# NETWORK_RS485.net
KiCad netlist of a schematic drawn in Altium Designer
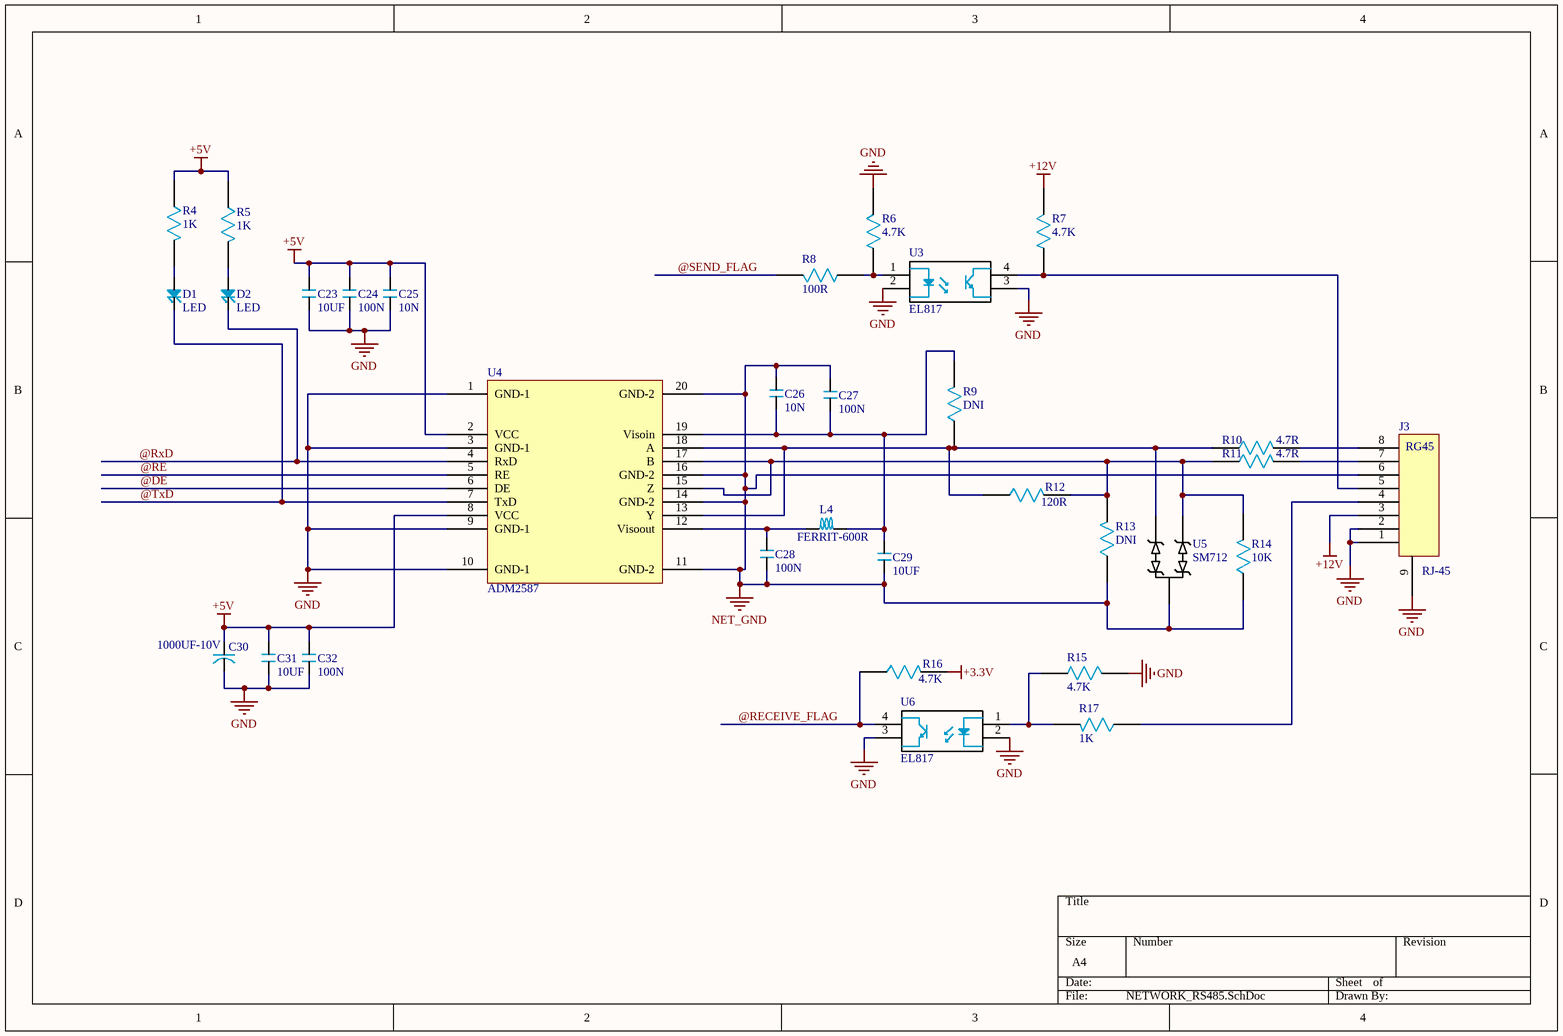
[diagram p0: NETWORK_RS485.SchDoc]

(export (version "E")
  (design (tool "Eeschema 10.0.6"))
  (components
    (comp (ref "C23") (value "10UF") (footprint "0603") (libsource (lib "R_L_C_V") (part "CAP")))
    (comp (ref "C24") (value "100N") (footprint "0603") (libsource (lib "R_L_C_V") (part "CAP")))
    (comp (ref "C25") (value "10N") (footprint "0603") (libsource (lib "R_L_C_V") (part "CAP")))
    (comp (ref "C26") (value "10N") (footprint "1206") (libsource (lib "R_L_C_V") (part "CAP")))
    (comp (ref "C27") (value "100N") (footprint "1206") (libsource (lib "R_L_C_V") (part "CAP")))
    (comp (ref "C28") (value "100N") (footprint "1206") (libsource (lib "R_L_C_V") (part "CAP")))
    (comp (ref "C29") (value "10UF") (footprint "1206") (libsource (lib "R_L_C_V") (part "CAP")))
    (comp (ref "C30") (value "1000UF-10V") (footprint "RB.2/.4") (libsource (lib "My_lib") (part "CAP_POL")))
    (comp (ref "C31") (value "10UF") (footprint "0603") (libsource (lib "R_L_C_V") (part "CAP")))
    (comp (ref "C32") (value "100N") (footprint "0603") (libsource (lib "R_L_C_V") (part "CAP")))
    (comp (ref "D1") (value "LED") (footprint "0603") (libsource (lib "My_lib") (part "LED")))
    (comp (ref "D2") (value "LED") (footprint "0603") (libsource (lib "My_lib") (part "LED")))
    (comp (ref "J3") (value "RJ-45") (footprint "RJ-45") (libsource (lib "CONNECTOR") (part "RJ-45")))
    (comp (ref "L4") (value "FERRIT-600R") (footprint "1206") (libsource (lib "R_L_C_V") (part "SELF")))
    (comp (ref "R4") (value "1K") (footprint "0603") (libsource (lib "My_lib") (part "RES")))
    (comp (ref "R5") (value "1K") (footprint "0603") (libsource (lib "My_lib") (part "RES")))
    (comp (ref "R6") (value "4.7K") (footprint "1206") (libsource (lib "My_lib") (part "RES")))
    (comp (ref "R7") (value "4.7K") (footprint "1206") (libsource (lib "My_lib") (part "RES")))
    (comp (ref "R8") (value "100R") (footprint "1206") (libsource (lib "My_lib") (part "RES")))
    (comp (ref "R9") (value "DNI") (footprint "1206") (libsource (lib "My_lib") (part "RES")))
    (comp (ref "R10") (value "4.7R") (footprint "1206") (libsource (lib "My_lib") (part "RES")))
    (comp (ref "R11") (value "4.7R") (footprint "1206") (libsource (lib "My_lib") (part "RES")))
    (comp (ref "R12") (value "120R") (footprint "1206") (libsource (lib "My_lib") (part "RES")))
    (comp (ref "R13") (value "DNI") (footprint "1206") (libsource (lib "My_lib") (part "RES")))
    (comp (ref "R14") (value "10K") (footprint "1206") (libsource (lib "My_lib") (part "RES")))
    (comp (ref "R15") (value "4.7K") (footprint "1206") (libsource (lib "My_lib") (part "RES")))
    (comp (ref "R16") (value "4.7K") (footprint "1206") (libsource (lib "My_lib") (part "RES")))
    (comp (ref "R17") (value "1K") (footprint "1206") (libsource (lib "My_lib") (part "RES")))
    (comp (ref "U3") (value "EL817") (footprint "DIP4") (libsource (lib "My_lib") (part "TLP521")))
    (comp (ref "U4") (value "ADM2587") (footprint "SOIC20_W") (libsource (lib "MY_IC") (part "AMD2582")))
    (comp (ref "U5") (value "SM712") (footprint "SOT-23") (libsource (lib "MY_IC") (part "SM712")))
    (comp (ref "U6") (value "EL817") (footprint "DIP4") (libsource (lib "My_lib") (part "TLP521")))
  )
  (nets
    (net (code "1") (name "+3.3V") (class "Default") (node (ref "R16") (pin "2") (pintype "passive")))
    (net (code "2") (name "+5V") (class "Default")
      (node (ref "C23") (pin "2") (pintype "passive"))
      (node (ref "C24") (pin "2") (pintype "passive"))
      (node (ref "C25") (pin "1") (pintype "passive"))
      (node (ref "C30") (pin "1") (pintype "passive"))
      (node (ref "C31") (pin "2") (pintype "passive"))
      (node (ref "C32") (pin "2") (pintype "passive"))
      (node (ref "R4") (pin "1") (pintype "passive"))
      (node (ref "R5") (pin "1") (pintype "passive"))
      (node (ref "U4") (pin "2") (pinfunction "VCC_2") (pintype "passive"))
      (node (ref "U4") (pin "8") (pinfunction "VCC_8") (pintype "passive"))
    )
    (net (code "3") (name "+12V") (class "Default")
      (node (ref "J3") (pin "3") (pinfunction "3_3") (pintype "passive"))
      (node (ref "R7") (pin "1") (pintype "passive"))
    )
    (net (code "4") (name "/@DE") (class "Default")
      (node (ref "U4") (pin "6") (pinfunction "DE_6") (pintype "passive"))
    )
    (net (code "5") (name "/@RE") (class "Default")
      (node (ref "U4") (pin "5") (pinfunction "RE_5") (pintype "passive"))
    )
    (net (code "6") (name "/@RECEIVE_FLAG") (class "Default")
      (node (ref "R16") (pin "1") (pintype "passive"))
      (node (ref "U6") (pin "4") (pintype "passive"))
    )
    (net (code "7") (name "/@RxD") (class "Default")
      (node (ref "D2") (pin "2") (pintype "passive"))
      (node (ref "U4") (pin "4") (pinfunction "RxD_4") (pintype "passive"))
    )
    (net (code "8") (name "/@SEND_FLAG") (class "Default") (node (ref "R8") (pin "1") (pintype "passive")))
    (net (code "9") (name "/@TxD") (class "Default")
      (node (ref "D1") (pin "2") (pintype "passive"))
      (node (ref "U4") (pin "7") (pinfunction "TxD_7") (pintype "passive"))
    )
    (net (code "10") (name "GND") (class "Default")
      (node (ref "C23") (pin "1") (pintype "passive"))
      (node (ref "C24") (pin "1") (pintype "passive"))
      (node (ref "C25") (pin "2") (pintype "passive"))
      (node (ref "C30") (pin "2") (pintype "passive"))
      (node (ref "C31") (pin "1") (pintype "passive"))
      (node (ref "C32") (pin "1") (pintype "passive"))
      (node (ref "J3") (pin "1") (pinfunction "1_1") (pintype "passive"))
      (node (ref "J3") (pin "2") (pinfunction "2_2") (pintype "passive"))
      (node (ref "J3") (pin "9") (pinfunction "9_9") (pintype "passive"))
      (node (ref "R15") (pin "1") (pintype "passive"))
      (node (ref "R6") (pin "1") (pintype "passive"))
      (node (ref "U3") (pin "2") (pintype "passive"))
      (node (ref "U3") (pin "3") (pintype "passive"))
      (node (ref "U4") (pin "1") (pinfunction "GND-1_1") (pintype "passive"))
      (node (ref "U4") (pin "10") (pinfunction "GND-1_10") (pintype "passive"))
      (node (ref "U4") (pin "3") (pinfunction "GND-1_3") (pintype "passive"))
      (node (ref "U4") (pin "9") (pinfunction "GND-1_9") (pintype "passive"))
      (node (ref "U6") (pin "2") (pintype "passive"))
      (node (ref "U6") (pin "3") (pintype "passive"))
    )
    (net (code "11") (name "NET_GND") (class "Default")
      (node (ref "C26") (pin "1") (pintype "passive"))
      (node (ref "C27") (pin "2") (pintype "passive"))
      (node (ref "C28") (pin "2") (pintype "passive"))
      (node (ref "C29") (pin "1") (pintype "passive"))
      (node (ref "J3") (pin "6") (pinfunction "6_6") (pintype "passive"))
      (node (ref "R13") (pin "1") (pintype "passive"))
      (node (ref "R14") (pin "1") (pintype "passive"))
      (node (ref "U4") (pin "11") (pinfunction "GND-2_11") (pintype "passive"))
      (node (ref "U4") (pin "14") (pinfunction "GND-2_14") (pintype "passive"))
      (node (ref "U4") (pin "16") (pinfunction "GND-2_16") (pintype "passive"))
      (node (ref "U4") (pin "20") (pinfunction "GND-2_20") (pintype "passive"))
      (node (ref "U5") (pin "3") (pinfunction "3_3") (pintype "passive"))
    )
    (net (code "12") (name "Net-(D1-Pad1)") (class "Default")
      (node (ref "D1") (pin "1") (pintype "passive"))
      (node (ref "R4") (pin "2") (pintype "passive"))
    )
    (net (code "13") (name "Net-(D2-Pad1)") (class "Default")
      (node (ref "D2") (pin "1") (pintype "passive"))
      (node (ref "R5") (pin "2") (pintype "passive"))
    )
    (net (code "14") (name "Net-(J3-Pad4)") (class "Default")
      (node (ref "J3") (pin "4") (pinfunction "4_4") (pintype "passive"))
      (node (ref "R17") (pin "1") (pintype "passive"))
    )
    (net (code "15") (name "Net-(J3-Pad5)") (class "Default")
      (node (ref "J3") (pin "5") (pinfunction "5_5") (pintype "passive"))
      (node (ref "R7") (pin "2") (pintype "passive"))
      (node (ref "U3") (pin "4") (pintype "passive"))
    )
    (net (code "16") (name "Net-(J3-Pad7)") (class "Default")
      (node (ref "J3") (pin "7") (pinfunction "7_7") (pintype "passive"))
      (node (ref "R11") (pin "2") (pintype "passive"))
    )
    (net (code "17") (name "Net-(J3-Pad8)") (class "Default")
      (node (ref "J3") (pin "8") (pinfunction "8_8") (pintype "passive"))
      (node (ref "R10") (pin "2") (pintype "passive"))
    )
    (net (code "18") (name "Net-(R6-Pad2)") (class "Default")
      (node (ref "R6") (pin "2") (pintype "passive"))
      (node (ref "R8") (pin "2") (pintype "passive"))
      (node (ref "U3") (pin "1") (pintype "passive"))
    )
    (net (code "19") (name "Net-(R15-Pad2)") (class "Default")
      (node (ref "R15") (pin "2") (pintype "passive"))
      (node (ref "R17") (pin "2") (pintype "passive"))
      (node (ref "U6") (pin "1") (pintype "passive"))
    )
    (net (code "20") (name "Net-(U4-A)") (class "Default")
      (node (ref "R10") (pin "1") (pintype "passive"))
      (node (ref "R12") (pin "1") (pintype "passive"))
      (node (ref "R9") (pin "1") (pintype "passive"))
      (node (ref "U4") (pin "13") (pinfunction "Y_13") (pintype "passive"))
      (node (ref "U4") (pin "18") (pinfunction "A_18") (pintype "passive"))
      (node (ref "U5") (pin "1") (pinfunction "1_1") (pintype "passive"))
    )
    (net (code "21") (name "Net-(U4-B)") (class "Default")
      (node (ref "R11") (pin "1") (pintype "passive"))
      (node (ref "R12") (pin "2") (pintype "passive"))
      (node (ref "R13") (pin "2") (pintype "passive"))
      (node (ref "R14") (pin "2") (pintype "passive"))
      (node (ref "U4") (pin "15") (pinfunction "Z_15") (pintype "passive"))
      (node (ref "U4") (pin "17") (pinfunction "B_17") (pintype "passive"))
      (node (ref "U5") (pin "2") (pinfunction "2_2") (pintype "passive"))
    )
    (net (code "22") (name "Net-(U4-Visoin)") (class "Default")
      (node (ref "C26") (pin "2") (pintype "passive"))
      (node (ref "C27") (pin "1") (pintype "passive"))
      (node (ref "C29") (pin "2") (pintype "passive"))
      (node (ref "L4") (pin "2") (pintype "passive"))
      (node (ref "R9") (pin "2") (pintype "passive"))
      (node (ref "U4") (pin "19") (pinfunction "Visoin_19") (pintype "passive"))
    )
    (net (code "23") (name "Net-(U4-Visoout)") (class "Default")
      (node (ref "C28") (pin "1") (pintype "passive"))
      (node (ref "L4") (pin "1") (pintype "passive"))
      (node (ref "U4") (pin "12") (pinfunction "Visoout_12") (pintype "passive"))
    )
  )
)
